# FMC_connector.net
KiCad netlist of a schematic drawn in Altium Designer
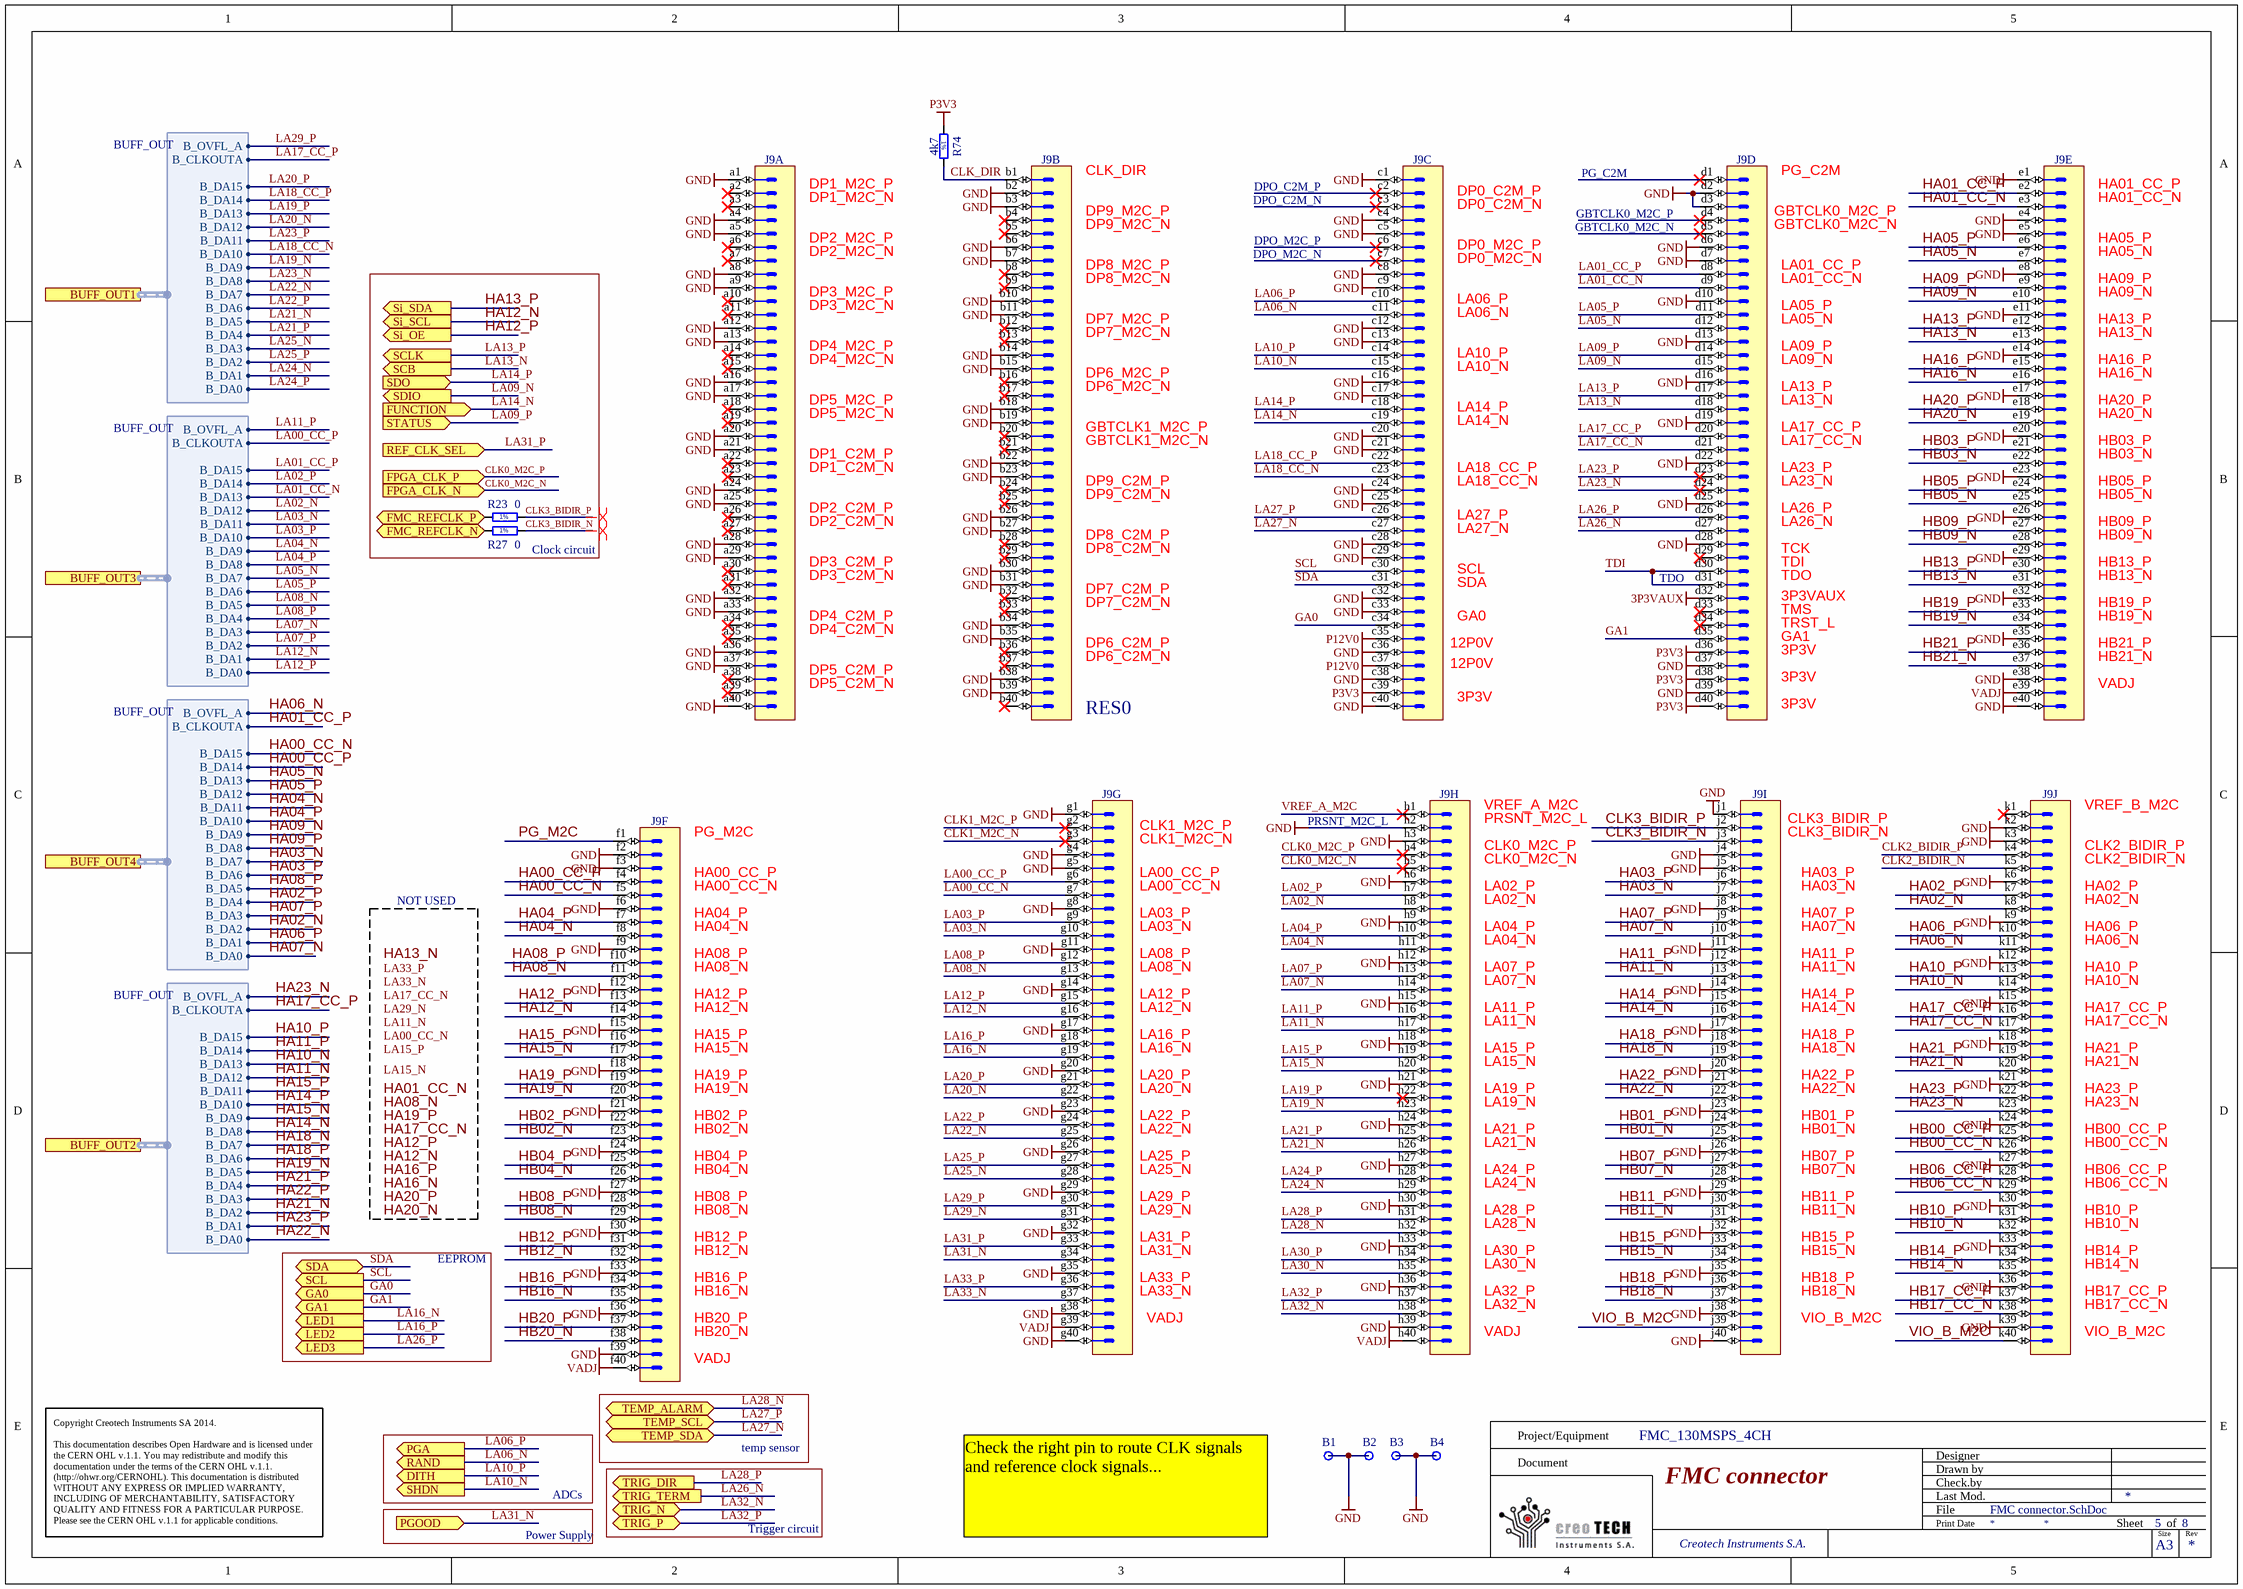
[diagram p0: FMC connector.SchDoc]

(export (version "E")
  (design (tool "Eeschema 10.0.6"))
  (components
    (comp (ref "B1")
      (value "Plated Hole")
      (footprint "MTG300_600")
      (description "Single Terminal Socket")
      (fields (field (name "PART NUMBER") "PLATED_HOLE3.0_PAD6.0") (field (name "AUTHOR") "CERN DEM JLC"))
      (libsource (lib "Eletro-mechanical") (part "Single Terminal Socket"))
    )
    (comp (ref "B2")
      (value "Plated Hole")
      (footprint "MTG300_600")
      (description "Single Terminal Socket")
      (fields (field (name "PART NUMBER") "PLATED_HOLE3.0_PAD6.0") (field (name "AUTHOR") "CERN DEM JLC"))
      (libsource (lib "Eletro-mechanical") (part "Single Terminal Socket"))
    )
    (comp (ref "B3")
      (value "Plated Hole")
      (footprint "MTG300_600")
      (description "Single Terminal Socket")
      (fields (field (name "PART NUMBER") "PLATED_HOLE3.0_PAD6.0") (field (name "AUTHOR") "CERN DEM JLC"))
      (libsource (lib "Eletro-mechanical") (part "Single Terminal Socket"))
    )
    (comp (ref "B4")
      (value "Plated Hole")
      (footprint "MTG300_600")
      (description "Single Terminal Socket")
      (fields (field (name "PART NUMBER") "PLATED_HOLE3.0_PAD6.0") (field (name "AUTHOR") "CERN DEM JLC"))
      (libsource (lib "Eletro-mechanical") (part "Single Terminal Socket"))
    )
    (comp (ref "J9")
      (value "VITA 57")
      (footprint "SAMTEC_ASP-134488-01")
      (description "Connector VITA 57, 400 Male contacts in 10 row abcdefghj")
      (fields
        (field (name "PART NUMBER") "SAMTEC_ASP-134488-01")
        (field (name "MANUFACTURER") "SAMTEC")
        (field (name "AUTHOR") "CERN DEM JLC")
      )
      (libsource (lib "Connectors") (part "Connector VITA 57 400 Male (abcdefghjk)"))
    )
    (comp (ref "R23")
      (value "0")
      (footprint "RESC1005X40N")
      (description "Resistor - 1%")
      (fields
        (field (name "PART NUMBER") "R0402_0R_JUMPER")
        (field (name "MANUFACTURER") "GENERIC")
        (field (name "AUTHOR") "CERN DEM JLC")
      )
      (libsource (lib "Resistors") (part "Resistor - 1%"))
    )
    (comp (ref "R27")
      (value "0")
      (footprint "RESC1005X40N")
      (description "Resistor - 1%")
      (fields
        (field (name "PART NUMBER") "R0402_0R_JUMPER")
        (field (name "MANUFACTURER") "GENERIC")
        (field (name "AUTHOR") "CERN DEM JLC")
      )
      (libsource (lib "Resistors") (part "Resistor - 1%"))
    )
    (comp (ref "R74")
      (value "4k7")
      (footprint "RESC1608X55N")
      (description "Resistor - 1%")
      (fields
        (field (name "PART NUMBER") "R0603_4K7_1%_0.1W_100PPM")
        (field (name "POWER") "0.1W")
        (field (name "AUTHOR") "CERN DEM JLC")
      )
      (libsource (lib "Resistors") (part "Resistor - 1%"))
    )
  )
  (nets
    (net (code "2") (name "/CLK0_M2C_N") (class "Default")
      (node (ref "J9") (pin "h5") (pinfunction "h5_h5") (pintype "bidirectional+no_connect"))
    )
    (net (code "3") (name "/CLK0_M2C_P") (class "Default")
      (node (ref "J9") (pin "h4") (pinfunction "h4_h4") (pintype "bidirectional+no_connect"))
    )
    (net (code "4") (name "/CLK1_M2C_N") (class "Default")
      (node (ref "J9") (pin "g3") (pinfunction "g3_g3") (pintype "bidirectional+no_connect"))
    )
    (net (code "5") (name "/CLK1_M2C_P") (class "Default")
      (node (ref "J9") (pin "g2") (pinfunction "g2_g2") (pintype "bidirectional+no_connect"))
    )
    (net (code "6") (name "/CLK2_BIDIR_N") (class "Default")
      (node (ref "J9") (pin "k5") (pinfunction "k5_k5") (pintype "bidirectional"))
    )
    (net (code "7") (name "/CLK2_BIDIR_P") (class "Default")
      (node (ref "J9") (pin "k4") (pinfunction "k4_k4") (pintype "bidirectional"))
    )
    (net (code "8") (name "/CLK3_BIDIR_N") (class "Default")
      (node (ref "J9") (pin "j3") (pinfunction "j3_j3") (pintype "bidirectional"))
      (node (ref "R27") (pin "2") (pinfunction "2_2") (pintype "passive"))
    )
    (net (code "9") (name "/CLK3_BIDIR_P") (class "Default")
      (node (ref "J9") (pin "j2") (pinfunction "j2_j2") (pintype "bidirectional"))
      (node (ref "R23") (pin "2") (pinfunction "2_2") (pintype "passive"))
    )
    (net (code "10") (name "/CLK_DIR") (class "Default")
      (node (ref "J9") (pin "b1") (pinfunction "b1_b1") (pintype "bidirectional"))
      (node (ref "R74") (pin "2") (pinfunction "2_2") (pintype "passive"))
    )
    (net (code "11") (name "/FMC_REFCLK_N") (class "Default")
      (node (ref "R27") (pin "1") (pinfunction "1_1") (pintype "passive"))
    )
    (net (code "12") (name "/FMC_REFCLK_P") (class "Default")
      (node (ref "R23") (pin "1") (pinfunction "1_1") (pintype "passive"))
    )
    (net (code "13") (name "/GA0") (class "Default")
      (node (ref "J9") (pin "c34") (pinfunction "c34_c34") (pintype "bidirectional"))
    )
    (net (code "14") (name "/GA1") (class "Default")
      (node (ref "J9") (pin "d35") (pinfunction "d35_d35") (pintype "bidirectional"))
    )
    (net (code "15") (name "/HA00_CC_N") (class "Default")
      (node (ref "J9") (pin "f5") (pinfunction "f5_f5") (pintype "bidirectional"))
    )
    (net (code "16") (name "/HA00_CC_P") (class "Default")
      (node (ref "J9") (pin "f4") (pinfunction "f4_f4") (pintype "bidirectional"))
    )
    (net (code "17") (name "/HA01_CC_N") (class "Default")
      (node (ref "J9") (pin "e3") (pinfunction "e3_e3") (pintype "bidirectional"))
    )
    (net (code "18") (name "/HA01_CC_P") (class "Default")
      (node (ref "J9") (pin "e2") (pinfunction "e2_e2") (pintype "bidirectional"))
    )
    (net (code "19") (name "/HA02_N") (class "Default")
      (node (ref "J9") (pin "k8") (pinfunction "k8_k8") (pintype "bidirectional"))
    )
    (net (code "20") (name "/HA02_P") (class "Default")
      (node (ref "J9") (pin "k7") (pinfunction "k7_k7") (pintype "bidirectional"))
    )
    (net (code "21") (name "/HA03_N") (class "Default")
      (node (ref "J9") (pin "j7") (pinfunction "j7_j7") (pintype "bidirectional"))
    )
    (net (code "22") (name "/HA03_P") (class "Default")
      (node (ref "J9") (pin "j6") (pinfunction "j6_j6") (pintype "bidirectional"))
    )
    (net (code "23") (name "/HA04_N") (class "Default")
      (node (ref "J9") (pin "f8") (pinfunction "f8_f8") (pintype "bidirectional"))
    )
    (net (code "24") (name "/HA04_P") (class "Default")
      (node (ref "J9") (pin "f7") (pinfunction "f7_f7") (pintype "bidirectional"))
    )
    (net (code "25") (name "/HA05_N") (class "Default")
      (node (ref "J9") (pin "e7") (pinfunction "e7_e7") (pintype "bidirectional"))
    )
    (net (code "26") (name "/HA05_P") (class "Default")
      (node (ref "J9") (pin "e6") (pinfunction "e6_e6") (pintype "bidirectional"))
    )
    (net (code "27") (name "/HA06_N") (class "Default")
      (node (ref "J9") (pin "k11") (pinfunction "k11_k11") (pintype "bidirectional"))
    )
    (net (code "28") (name "/HA06_P") (class "Default")
      (node (ref "J9") (pin "k10") (pinfunction "k10_k10") (pintype "bidirectional"))
    )
    (net (code "29") (name "/HA07_N") (class "Default")
      (node (ref "J9") (pin "j10") (pinfunction "j10_j10") (pintype "bidirectional"))
    )
    (net (code "30") (name "/HA07_P") (class "Default")
      (node (ref "J9") (pin "j9") (pinfunction "j9_j9") (pintype "bidirectional"))
    )
    (net (code "31") (name "/HA08_N") (class "Default")
      (node (ref "J9") (pin "f11") (pinfunction "f11_f11") (pintype "bidirectional"))
    )
    (net (code "32") (name "/HA08_P") (class "Default")
      (node (ref "J9") (pin "f10") (pinfunction "f10_f10") (pintype "bidirectional"))
    )
    (net (code "33") (name "/HA09_N") (class "Default")
      (node (ref "J9") (pin "e10") (pinfunction "e10_e10") (pintype "bidirectional"))
    )
    (net (code "34") (name "/HA09_P") (class "Default")
      (node (ref "J9") (pin "e9") (pinfunction "e9_e9") (pintype "bidirectional"))
    )
    (net (code "35") (name "/HA10_N") (class "Default")
      (node (ref "J9") (pin "k14") (pinfunction "k14_k14") (pintype "bidirectional"))
    )
    (net (code "36") (name "/HA10_P") (class "Default")
      (node (ref "J9") (pin "k13") (pinfunction "k13_k13") (pintype "bidirectional"))
    )
    (net (code "37") (name "/HA11_N") (class "Default")
      (node (ref "J9") (pin "j13") (pinfunction "j13_j13") (pintype "bidirectional"))
    )
    (net (code "38") (name "/HA11_P") (class "Default")
      (node (ref "J9") (pin "j12") (pinfunction "j12_j12") (pintype "bidirectional"))
    )
    (net (code "39") (name "/HA12_N") (class "Default")
      (node (ref "J9") (pin "f14") (pinfunction "f14_f14") (pintype "bidirectional"))
    )
    (net (code "40") (name "/HA12_P") (class "Default")
      (node (ref "J9") (pin "f13") (pinfunction "f13_f13") (pintype "bidirectional"))
    )
    (net (code "41") (name "/HA13_N") (class "Default")
      (node (ref "J9") (pin "e13") (pinfunction "e13_e13") (pintype "bidirectional"))
    )
    (net (code "42") (name "/HA13_P") (class "Default")
      (node (ref "J9") (pin "e12") (pinfunction "e12_e12") (pintype "bidirectional"))
    )
    (net (code "43") (name "/HA14_N") (class "Default")
      (node (ref "J9") (pin "j16") (pinfunction "j16_j16") (pintype "bidirectional"))
    )
    (net (code "44") (name "/HA14_P") (class "Default")
      (node (ref "J9") (pin "j15") (pinfunction "j15_j15") (pintype "bidirectional"))
    )
    (net (code "45") (name "/HA15_N") (class "Default")
      (node (ref "J9") (pin "f17") (pinfunction "f17_f17") (pintype "bidirectional"))
    )
    (net (code "46") (name "/HA15_P") (class "Default")
      (node (ref "J9") (pin "f16") (pinfunction "f16_f16") (pintype "bidirectional"))
    )
    (net (code "47") (name "/HA16_N") (class "Default")
      (node (ref "J9") (pin "e16") (pinfunction "e16_e16") (pintype "bidirectional"))
    )
    (net (code "48") (name "/HA16_P") (class "Default")
      (node (ref "J9") (pin "e15") (pinfunction "e15_e15") (pintype "bidirectional"))
    )
    (net (code "49") (name "/HA17_CC_N") (class "Default")
      (node (ref "J9") (pin "k17") (pinfunction "k17_k17") (pintype "bidirectional"))
    )
    (net (code "50") (name "/HA17_CC_P") (class "Default")
      (node (ref "J9") (pin "k16") (pinfunction "k16_k16") (pintype "bidirectional"))
    )
    (net (code "51") (name "/HA18_N") (class "Default")
      (node (ref "J9") (pin "j19") (pinfunction "j19_j19") (pintype "bidirectional"))
    )
    (net (code "52") (name "/HA18_P") (class "Default")
      (node (ref "J9") (pin "j18") (pinfunction "j18_j18") (pintype "bidirectional"))
    )
    (net (code "53") (name "/HA19_N") (class "Default")
      (node (ref "J9") (pin "f20") (pinfunction "f20_f20") (pintype "bidirectional"))
    )
    (net (code "54") (name "/HA19_P") (class "Default")
      (node (ref "J9") (pin "f19") (pinfunction "f19_f19") (pintype "bidirectional"))
    )
    (net (code "55") (name "/HA20_N") (class "Default")
      (node (ref "J9") (pin "e19") (pinfunction "e19_e19") (pintype "bidirectional"))
    )
    (net (code "56") (name "/HA20_P") (class "Default")
      (node (ref "J9") (pin "e18") (pinfunction "e18_e18") (pintype "bidirectional"))
    )
    (net (code "57") (name "/HA21_N") (class "Default")
      (node (ref "J9") (pin "k20") (pinfunction "k20_k20") (pintype "bidirectional"))
    )
    (net (code "58") (name "/HA21_P") (class "Default")
      (node (ref "J9") (pin "k19") (pinfunction "k19_k19") (pintype "bidirectional"))
    )
    (net (code "59") (name "/HA22_N") (class "Default")
      (node (ref "J9") (pin "j22") (pinfunction "j22_j22") (pintype "bidirectional"))
    )
    (net (code "60") (name "/HA22_P") (class "Default")
      (node (ref "J9") (pin "j21") (pinfunction "j21_j21") (pintype "bidirectional"))
    )
    (net (code "61") (name "/HA23_N") (class "Default")
      (node (ref "J9") (pin "k23") (pinfunction "k23_k23") (pintype "bidirectional"))
    )
    (net (code "62") (name "/HA23_P") (class "Default")
      (node (ref "J9") (pin "k22") (pinfunction "k22_k22") (pintype "bidirectional"))
    )
    (net (code "63") (name "/HB00_CC_N") (class "Default")
      (node (ref "J9") (pin "k26") (pinfunction "k26_k26") (pintype "bidirectional"))
    )
    (net (code "64") (name "/HB00_CC_P") (class "Default")
      (node (ref "J9") (pin "k25") (pinfunction "k25_k25") (pintype "bidirectional"))
    )
    (net (code "65") (name "/HB01_N") (class "Default")
      (node (ref "J9") (pin "j25") (pinfunction "j25_j25") (pintype "bidirectional"))
    )
    (net (code "66") (name "/HB01_P") (class "Default")
      (node (ref "J9") (pin "j24") (pinfunction "j24_j24") (pintype "bidirectional"))
    )
    (net (code "67") (name "/HB02_N") (class "Default")
      (node (ref "J9") (pin "f23") (pinfunction "f23_f23") (pintype "bidirectional"))
    )
    (net (code "68") (name "/HB02_P") (class "Default")
      (node (ref "J9") (pin "f22") (pinfunction "f22_f22") (pintype "bidirectional"))
    )
    (net (code "69") (name "/HB03_N") (class "Default")
      (node (ref "J9") (pin "e22") (pinfunction "e22_e22") (pintype "bidirectional"))
    )
    (net (code "70") (name "/HB03_P") (class "Default")
      (node (ref "J9") (pin "e21") (pinfunction "e21_e21") (pintype "bidirectional"))
    )
    (net (code "71") (name "/HB04_N") (class "Default")
      (node (ref "J9") (pin "f26") (pinfunction "f26_f26") (pintype "bidirectional"))
    )
    (net (code "72") (name "/HB04_P") (class "Default")
      (node (ref "J9") (pin "f25") (pinfunction "f25_f25") (pintype "bidirectional"))
    )
    (net (code "73") (name "/HB05_N") (class "Default")
      (node (ref "J9") (pin "e25") (pinfunction "e25_e25") (pintype "bidirectional"))
    )
    (net (code "74") (name "/HB05_P") (class "Default")
      (node (ref "J9") (pin "e24") (pinfunction "e24_e24") (pintype "bidirectional"))
    )
    (net (code "75") (name "/HB06_CC_N") (class "Default")
      (node (ref "J9") (pin "k29") (pinfunction "k29_k29") (pintype "bidirectional"))
    )
    (net (code "76") (name "/HB06_CC_P") (class "Default")
      (node (ref "J9") (pin "k28") (pinfunction "k28_k28") (pintype "bidirectional"))
    )
    (net (code "77") (name "/HB07_N") (class "Default")
      (node (ref "J9") (pin "j28") (pinfunction "j28_j28") (pintype "bidirectional"))
    )
    (net (code "78") (name "/HB07_P") (class "Default")
      (node (ref "J9") (pin "j27") (pinfunction "j27_j27") (pintype "bidirectional"))
    )
    (net (code "79") (name "/HB08_N") (class "Default")
      (node (ref "J9") (pin "f29") (pinfunction "f29_f29") (pintype "bidirectional"))
    )
    (net (code "80") (name "/HB08_P") (class "Default")
      (node (ref "J9") (pin "f28") (pinfunction "f28_f28") (pintype "bidirectional"))
    )
    (net (code "81") (name "/HB09_N") (class "Default")
      (node (ref "J9") (pin "e28") (pinfunction "e28_e28") (pintype "bidirectional"))
    )
    (net (code "82") (name "/HB09_P") (class "Default")
      (node (ref "J9") (pin "e27") (pinfunction "e27_e27") (pintype "bidirectional"))
    )
    (net (code "83") (name "/HB10_N") (class "Default")
      (node (ref "J9") (pin "k32") (pinfunction "k32_k32") (pintype "bidirectional"))
    )
    (net (code "84") (name "/HB10_P") (class "Default")
      (node (ref "J9") (pin "k31") (pinfunction "k31_k31") (pintype "bidirectional"))
    )
    (net (code "85") (name "/HB11_N") (class "Default")
      (node (ref "J9") (pin "j31") (pinfunction "j31_j31") (pintype "bidirectional"))
    )
    (net (code "86") (name "/HB11_P") (class "Default")
      (node (ref "J9") (pin "j30") (pinfunction "j30_j30") (pintype "bidirectional"))
    )
    (net (code "87") (name "/HB12_N") (class "Default")
      (node (ref "J9") (pin "f32") (pinfunction "f32_f32") (pintype "bidirectional"))
    )
    (net (code "88") (name "/HB12_P") (class "Default")
      (node (ref "J9") (pin "f31") (pinfunction "f31_f31") (pintype "bidirectional"))
    )
    (net (code "89") (name "/HB13_N") (class "Default")
      (node (ref "J9") (pin "e31") (pinfunction "e31_e31") (pintype "bidirectional"))
    )
    (net (code "90") (name "/HB13_P") (class "Default")
      (node (ref "J9") (pin "e30") (pinfunction "e30_e30") (pintype "bidirectional"))
    )
    (net (code "91") (name "/HB14_N") (class "Default")
      (node (ref "J9") (pin "k35") (pinfunction "k35_k35") (pintype "bidirectional"))
    )
    (net (code "92") (name "/HB14_P") (class "Default")
      (node (ref "J9") (pin "k34") (pinfunction "k34_k34") (pintype "bidirectional"))
    )
    (net (code "93") (name "/HB15_N") (class "Default")
      (node (ref "J9") (pin "j34") (pinfunction "j34_j34") (pintype "bidirectional"))
    )
    (net (code "94") (name "/HB15_P") (class "Default")
      (node (ref "J9") (pin "j33") (pinfunction "j33_j33") (pintype "bidirectional"))
    )
    (net (code "95") (name "/HB16_N") (class "Default")
      (node (ref "J9") (pin "f35") (pinfunction "f35_f35") (pintype "bidirectional"))
    )
    (net (code "96") (name "/HB16_P") (class "Default")
      (node (ref "J9") (pin "f34") (pinfunction "f34_f34") (pintype "bidirectional"))
    )
    (net (code "97") (name "/HB17_CC_N") (class "Default")
      (node (ref "J9") (pin "k38") (pinfunction "k38_k38") (pintype "bidirectional"))
    )
    (net (code "98") (name "/HB17_CC_P") (class "Default")
      (node (ref "J9") (pin "k37") (pinfunction "k37_k37") (pintype "bidirectional"))
    )
    (net (code "99") (name "/HB18_N") (class "Default")
      (node (ref "J9") (pin "j37") (pinfunction "j37_j37") (pintype "bidirectional"))
    )
    (net (code "100") (name "/HB18_P") (class "Default")
      (node (ref "J9") (pin "j36") (pinfunction "j36_j36") (pintype "bidirectional"))
    )
    (net (code "101") (name "/HB19_N") (class "Default")
      (node (ref "J9") (pin "e34") (pinfunction "e34_e34") (pintype "bidirectional"))
    )
    (net (code "102") (name "/HB19_P") (class "Default")
      (node (ref "J9") (pin "e33") (pinfunction "e33_e33") (pintype "bidirectional"))
    )
    (net (code "103") (name "/HB20_N") (class "Default")
      (node (ref "J9") (pin "f38") (pinfunction "f38_f38") (pintype "bidirectional"))
    )
    (net (code "104") (name "/HB20_P") (class "Default")
      (node (ref "J9") (pin "f37") (pinfunction "f37_f37") (pintype "bidirectional"))
    )
    (net (code "105") (name "/HB21_N") (class "Default")
      (node (ref "J9") (pin "e37") (pinfunction "e37_e37") (pintype "bidirectional"))
    )
    (net (code "106") (name "/HB21_P") (class "Default")
      (node (ref "J9") (pin "e36") (pinfunction "e36_e36") (pintype "bidirectional"))
    )
    (net (code "107") (name "/LA00_CC_N") (class "Default")
      (node (ref "J9") (pin "g7") (pinfunction "g7_g7") (pintype "bidirectional"))
    )
    (net (code "108") (name "/LA00_CC_P") (class "Default")
      (node (ref "J9") (pin "g6") (pinfunction "g6_g6") (pintype "bidirectional"))
    )
    (net (code "109") (name "/LA01_CC_N") (class "Default")
      (node (ref "J9") (pin "d9") (pinfunction "d9_d9") (pintype "bidirectional"))
    )
    (net (code "110") (name "/LA01_CC_P") (class "Default")
      (node (ref "J9") (pin "d8") (pinfunction "d8_d8") (pintype "bidirectional"))
    )
    (net (code "111") (name "/LA02_N") (class "Default")
      (node (ref "J9") (pin "h8") (pinfunction "h8_h8") (pintype "bidirectional"))
    )
    (net (code "112") (name "/LA02_P") (class "Default")
      (node (ref "J9") (pin "h7") (pinfunction "h7_h7") (pintype "bidirectional"))
    )
    (net (code "113") (name "/LA03_N") (class "Default")
      (node (ref "J9") (pin "g10") (pinfunction "g10_g10") (pintype "bidirectional"))
    )
    (net (code "114") (name "/LA03_P") (class "Default")
      (node (ref "J9") (pin "g9") (pinfunction "g9_g9") (pintype "bidirectional"))
    )
    (net (code "115") (name "/LA04_N") (class "Default")
      (node (ref "J9") (pin "h11") (pinfunction "h11_h11") (pintype "bidirectional"))
    )
    (net (code "116") (name "/LA04_P") (class "Default")
      (node (ref "J9") (pin "h10") (pinfunction "h10_h10") (pintype "bidirectional"))
    )
    (net (code "117") (name "/LA05_N") (class "Default")
      (node (ref "J9") (pin "d12") (pinfunction "d12_d12") (pintype "bidirectional"))
    )
    (net (code "118") (name "/LA05_P") (class "Default")
      (node (ref "J9") (pin "d11") (pinfunction "d11_d11") (pintype "bidirectional"))
    )
    (net (code "119") (name "/LA06_N") (class "Default")
      (node (ref "J9") (pin "c11") (pinfunction "c11_c11") (pintype "bidirectional"))
    )
    (net (code "120") (name "/LA06_P") (class "Default")
      (node (ref "J9") (pin "c10") (pinfunction "c10_c10") (pintype "bidirectional"))
    )
    (net (code "121") (name "/LA07_N") (class "Default")
      (node (ref "J9") (pin "h14") (pinfunction "h14_h14") (pintype "bidirectional"))
    )
    (net (code "122") (name "/LA07_P") (class "Default")
      (node (ref "J9") (pin "h13") (pinfunction "h13_h13") (pintype "bidirectional"))
    )
    (net (code "123") (name "/LA08_N") (class "Default")
      (node (ref "J9") (pin "g13") (pinfunction "g13_g13") (pintype "bidirectional"))
    )
    (net (code "124") (name "/LA08_P") (class "Default")
      (node (ref "J9") (pin "g12") (pinfunction "g12_g12") (pintype "bidirectional"))
    )
    (net (code "125") (name "/LA09_N") (class "Default")
      (node (ref "J9") (pin "d15") (pinfunction "d15_d15") (pintype "bidirectional"))
    )
    (net (code "126") (name "/LA09_P") (class "Default")
      (node (ref "J9") (pin "d14") (pinfunction "d14_d14") (pintype "bidirectional"))
    )
    (net (code "127") (name "/LA10_N") (class "Default")
      (node (ref "J9") (pin "c15") (pinfunction "c15_c15") (pintype "bidirectional"))
    )
    (net (code "128") (name "/LA10_P") (class "Default")
      (node (ref "J9") (pin "c14") (pinfunction "c14_c14") (pintype "bidirectional"))
    )
    (net (code "129") (name "/LA11_N") (class "Default")
      (node (ref "J9") (pin "h17") (pinfunction "h17_h17") (pintype "bidirectional"))
    )
    (net (code "130") (name "/LA11_P") (class "Default")
      (node (ref "J9") (pin "h16") (pinfunction "h16_h16") (pintype "bidirectional"))
    )
    (net (code "131") (name "/LA12_N") (class "Default")
      (node (ref "J9") (pin "g16") (pinfunction "g16_g16") (pintype "bidirectional"))
    )
    (net (code "132") (name "/LA12_P") (class "Default")
      (node (ref "J9") (pin "g15") (pinfunction "g15_g15") (pintype "bidirectional"))
    )
    (net (code "133") (name "/LA13_N") (class "Default")
      (node (ref "J9") (pin "d18") (pinfunction "d18_d18") (pintype "bidirectional"))
    )
    (net (code "134") (name "/LA13_P") (class "Default")
      (node (ref "J9") (pin "d17") (pinfunction "d17_d17") (pintype "bidirectional"))
    )
    (net (code "135") (name "/LA14_N") (class "Default")
      (node (ref "J9") (pin "c19") (pinfunction "c19_c19") (pintype "bidirectional"))
    )
    (net (code "136") (name "/LA14_P") (class "Default")
      (node (ref "J9") (pin "c18") (pinfunction "c18_c18") (pintype "bidirectional"))
    )
    (net (code "137") (name "/LA15_N") (class "Default")
      (node (ref "J9") (pin "h20") (pinfunction "h20_h20") (pintype "bidirectional"))
    )
    (net (code "138") (name "/LA15_P") (class "Default")
      (node (ref "J9") (pin "h19") (pinfunction "h19_h19") (pintype "bidirectional"))
    )
    (net (code "139") (name "/LA16_N") (class "Default")
      (node (ref "J9") (pin "g19") (pinfunction "g19_g19") (pintype "bidirectional"))
    )
    (net (code "140") (name "/LA16_P") (class "Default")
      (node (ref "J9") (pin "g18") (pinfunction "g18_g18") (pintype "bidirectional"))
    )
    (net (code "141") (name "/LA17_CC_N") (class "Default")
      (node (ref "J9") (pin "d21") (pinfunction "d21_d21") (pintype "bidirectional"))
    )
    (net (code "142") (name "/LA17_CC_P") (class "Default")
      (node (ref "J9") (pin "d20") (pinfunction "d20_d20") (pintype "bidirectional"))
    )
    (net (code "143") (name "/LA18_CC_N") (class "Default")
      (node (ref "J9") (pin "c23") (pinfunction "c23_c23") (pintype "bidirectional"))
    )
    (net (code "144") (name "/LA18_CC_P") (class "Default")
      (node (ref "J9") (pin "c22") (pinfunction "c22_c22") (pintype "bidirectional"))
    )
    (net (code "145") (name "/LA19_N") (class "Default")
      (node (ref "J9") (pin "h23") (pinfunction "h23_h23") (pintype "bidirectional"))
    )
    (net (code "146") (name "/LA19_P") (class "Default")
      (node (ref "J9") (pin "h22") (pinfunction "h22_h22") (pintype "bidirectional+no_connect"))
    )
    (net (code "147") (name "/LA20_N") (class "Default")
      (node (ref "J9") (pin "g22") (pinfunction "g22_g22") (pintype "bidirectional"))
    )
    (net (code "148") (name "/LA20_P") (class "Default")
      (node (ref "J9") (pin "g21") (pinfunction "g21_g21") (pintype "bidirectional"))
    )
    (net (code "149") (name "/LA21_N") (class "Default")
      (node (ref "J9") (pin "h26") (pinfunction "h26_h26") (pintype "bidirectional"))
    )
    (net (code "150") (name "/LA21_P") (class "Default")
      (node (ref "J9") (pin "h25") (pinfunction "h25_h25") (pintype "bidirectional"))
    )
    (net (code "151") (name "/LA22_N") (class "Default")
      (node (ref "J9") (pin "g25") (pinfunction "g25_g25") (pintype "bidirectional"))
    )
    (net (code "152") (name "/LA22_P") (class "Default")
      (node (ref "J9") (pin "g24") (pinfunction "g24_g24") (pintype "bidirectional"))
    )
    (net (code "153") (name "/LA23_N") (class "Default")
      (node (ref "J9") (pin "d24") (pinfunction "d24_d24") (pintype "bidirectional+no_connect"))
    )
    (net (code "154") (name "/LA23_P") (class "Default")
      (node (ref "J9") (pin "d23") (pinfunction "d23_d23") (pintype "bidirectional+no_connect"))
    )
    (net (code "155") (name "/LA24_N") (class "Default")
      (node (ref "J9") (pin "h29") (pinfunction "h29_h29") (pintype "bidirectional"))
    )
    (net (code "156") (name "/LA24_P") (class "Default")
      (node (ref "J9") (pin "h28") (pinfunction "h28_h28") (pintype "bidirectional"))
    )
    (net (code "157") (name "/LA25_N") (class "Default")
      (node (ref "J9") (pin "g28") (pinfunction "g28_g28") (pintype "bidirectional"))
    )
    (net (code "158") (name "/LA25_P") (class "Default")
      (node (ref "J9") (pin "g27") (pinfunction "g27_g27") (pintype "bidirectional"))
    )
    (net (code "159") (name "/LA26_N") (class "Default")
      (node (ref "J9") (pin "d27") (pinfunction "d27_d27") (pintype "bidirectional"))
    )
    (net (code "160") (name "/LA26_P") (class "Default")
      (node (ref "J9") (pin "d26") (pinfunction "d26_d26") (pintype "bidirectional"))
    )
    (net (code "161") (name "/LA27_N") (class "Default")
      (node (ref "J9") (pin "c27") (pinfunction "c27_c27") (pintype "bidirectional"))
    )
    (net (code "162") (name "/LA27_P") (class "Default")
      (node (ref "J9") (pin "c26") (pinfunction "c26_c26") (pintype "bidirectional"))
    )
    (net (code "163") (name "/LA28_N") (class "Default")
      (node (ref "J9") (pin "h32") (pinfunction "h32_h32") (pintype "bidirectional"))
    )
    (net (code "164") (name "/LA28_P") (class "Default")
      (node (ref "J9") (pin "h31") (pinfunction "h31_h31") (pintype "bidirectional"))
    )
    (net (code "165") (name "/LA29_N") (class "Default")
      (node (ref "J9") (pin "g31") (pinfunction "g31_g31") (pintype "bidirectional"))
    )
    (net (code "166") (name "/LA29_P") (class "Default")
      (node (ref "J9") (pin "g30") (pinfunction "g30_g30") (pintype "bidirectional"))
    )
    (net (code "167") (name "/LA30_N") (class "Default")
      (node (ref "J9") (pin "h35") (pinfunction "h35_h35") (pintype "bidirectional"))
    )
    (net (code "168") (name "/LA30_P") (class "Default")
      (node (ref "J9") (pin "h34") (pinfunction "h34_h34") (pintype "bidirectional"))
    )
    (net (code "169") (name "/LA31_N") (class "Default")
      (node (ref "J9") (pin "g34") (pinfunction "g34_g34") (pintype "bidirectional"))
    )
    (net (code "170") (name "/LA31_P") (class "Default")
      (node (ref "J9") (pin "g33") (pinfunction "g33_g33") (pintype "bidirectional"))
    )
    (net (code "171") (name "/LA32_N") (class "Default")
      (node (ref "J9") (pin "h38") (pinfunction "h38_h38") (pintype "bidirectional"))
    )
    (net (code "172") (name "/LA32_P") (class "Default")
      (node (ref "J9") (pin "h37") (pinfunction "h37_h37") (pintype "bidirectional"))
    )
    (net (code "173") (name "/LA33_N") (class "Default")
      (node (ref "J9") (pin "g37") (pinfunction "g37_g37") (pintype "bidirectional"))
    )
    (net (code "174") (name "/LA33_P") (class "Default")
      (node (ref "J9") (pin "g36") (pinfunction "g36_g36") (pintype "bidirectional"))
    )
    (net (code "175") (name "/PG_M2C") (class "Default")
      (node (ref "J9") (pin "f1") (pinfunction "f1_f1") (pintype "bidirectional"))
    )
    (net (code "176") (name "/SCL") (class "Default")
      (node (ref "J9") (pin "c30") (pinfunction "c30_c30") (pintype "bidirectional"))
    )
    (net (code "177") (name "/SDA") (class "Default")
      (node (ref "J9") (pin "c31") (pinfunction "c31_c31") (pintype "bidirectional"))
    )
    (net (code "178") (name "/TDI") (class "Default")
      (node (ref "J9") (pin "d30") (pinfunction "d30_d30") (pintype "bidirectional"))
      (node (ref "J9") (pin "d31") (pinfunction "d31_d31") (pintype "bidirectional"))
    )
    (net (code "179") (name "/VIO_B_M2C") (class "Default")
      (node (ref "J9") (pin "j39") (pinfunction "j39_j39") (pintype "bidirectional"))
      (node (ref "J9") (pin "k40") (pinfunction "k40_k40") (pintype "bidirectional"))
    )
    (net (code "180") (name "/VREF_A_M2C") (class "Default")
      (node (ref "J9") (pin "h1") (pinfunction "h1_h1") (pintype "bidirectional+no_connect"))
    )
    (net (code "182") (name "3P3VAUX") (class "Default")
      (node (ref "J9") (pin "d32") (pinfunction "d32_d32") (pintype "bidirectional"))
    )
    (net (code "183") (name "GND") (class "Default")
      (node (ref "B1") (pin "1") (pinfunction "1_1") (pintype "bidirectional"))
      (node (ref "B2") (pin "1") (pinfunction "1_1") (pintype "bidirectional"))
      (node (ref "B3") (pin "1") (pinfunction "1_1") (pintype "bidirectional"))
      (node (ref "B4") (pin "1") (pinfunction "1_1") (pintype "bidirectional"))
      (node (ref "J9") (pin "a1") (pinfunction "a1_a1") (pintype "bidirectional"))
      (node (ref "J9") (pin "a12") (pinfunction "a12_a12") (pintype "bidirectional"))
      (node (ref "J9") (pin "a13") (pinfunction "a13_a13") (pintype "bidirectional"))
      (node (ref "J9") (pin "a16") (pinfunction "a16_a16") (pintype "bidirectional"))
      (node (ref "J9") (pin "a17") (pinfunction "a17_a17") (pintype "bidirectional"))
      (node (ref "J9") (pin "a20") (pinfunction "a20_a20") (pintype "bidirectional"))
      (node (ref "J9") (pin "a21") (pinfunction "a21_a21") (pintype "bidirectional"))
      (node (ref "J9") (pin "a24") (pinfunction "a24_a24") (pintype "bidirectional"))
      (node (ref "J9") (pin "a25") (pinfunction "a25_a25") (pintype "bidirectional"))
      (node (ref "J9") (pin "a28") (pinfunction "a28_a28") (pintype "bidirectional"))
      (node (ref "J9") (pin "a29") (pinfunction "a29_a29") (pintype "bidirectional"))
      (node (ref "J9") (pin "a32") (pinfunction "a32_a32") (pintype "bidirectional"))
      (node (ref "J9") (pin "a33") (pinfunction "a33_a33") (pintype "bidirectional"))
      (node (ref "J9") (pin "a36") (pinfunction "a36_a36") (pintype "bidirectional"))
      (node (ref "J9") (pin "a37") (pinfunction "a37_a37") (pintype "bidirectional"))
      (node (ref "J9") (pin "a4") (pinfunction "a4_a4") (pintype "bidirectional"))
      (node (ref "J9") (pin "a40") (pinfunction "a40_a40") (pintype "bidirectional"))
      (node (ref "J9") (pin "a5") (pinfunction "a5_a5") (pintype "bidirectional"))
      (node (ref "J9") (pin "a8") (pinfunction "a8_a8") (pintype "bidirectional"))
      (node (ref "J9") (pin "a9") (pinfunction "a9_a9") (pintype "bidirectional"))
      (node (ref "J9") (pin "b10") (pinfunction "b10_b10") (pintype "bidirectional"))
      (node (ref "J9") (pin "b11") (pinfunction "b11_b11") (pintype "bidirectional"))
      (node (ref "J9") (pin "b14") (pinfunction "b14_b14") (pintype "bidirectional"))
      (node (ref "J9") (pin "b15") (pinfunction "b15_b15") (pintype "bidirectional"))
      (node (ref "J9") (pin "b18") (pinfunction "b18_b18") (pintype "bidirectional"))
      (node (ref "J9") (pin "b19") (pinfunction "b19_b19") (pintype "bidirectional"))
      (node (ref "J9") (pin "b2") (pinfunction "b2_b2") (pintype "bidirectional"))
      (node (ref "J9") (pin "b22") (pinfunction "b22_b22") (pintype "bidirectional"))
      (node (ref "J9") (pin "b23") (pinfunction "b23_b23") (pintype "bidirectional"))
      (node (ref "J9") (pin "b26") (pinfunction "b26_b26") (pintype "bidirectional"))
      (node (ref "J9") (pin "b27") (pinfunction "b27_b27") (pintype "bidirectional"))
      (node (ref "J9") (pin "b3") (pinfunction "b3_b3") (pintype "bidirectional"))
      (node (ref "J9") (pin "b30") (pinfunction "b30_b30") (pintype "bidirectional"))
      (node (ref "J9") (pin "b31") (pinfunction "b31_b31") (pintype "bidirectional"))
      (node (ref "J9") (pin "b34") (pinfunction "b34_b34") (pintype "bidirectional"))
      (node (ref "J9") (pin "b35") (pinfunction "b35_b35") (pintype "bidirectional"))
      (node (ref "J9") (pin "b38") (pinfunction "b38_b38") (pintype "bidirectional"))
      (node (ref "J9") (pin "b39") (pinfunction "b39_b39") (pintype "bidirectional"))
      (node (ref "J9") (pin "b6") (pinfunction "b6_b6") (pintype "bidirectional"))
      (node (ref "J9") (pin "b7") (pinfunction "b7_b7") (pintype "bidirectional"))
      (node (ref "J9") (pin "c1") (pinfunction "c1_c1") (pintype "bidirectional"))
      (node (ref "J9") (pin "c12") (pinfunction "c12_c12") (pintype "bidirectional"))
      (node (ref "J9") (pin "c13") (pinfunction "c13_c13") (pintype "bidirectional"))
      (node (ref "J9") (pin "c16") (pinfunction "c16_c16") (pintype "bidirectional"))
      (node (ref "J9") (pin "c17") (pinfunction "c17_c17") (pintype "bidirectional"))
      (node (ref "J9") (pin "c20") (pinfunction "c20_c20") (pintype "bidirectional"))
      (node (ref "J9") (pin "c21") (pinfunction "c21_c21") (pintype "bidirectional"))
      (node (ref "J9") (pin "c24") (pinfunction "c24_c24") (pintype "bidirectional"))
      (node (ref "J9") (pin "c25") (pinfunction "c25_c25") (pintype "bidirectional"))
      (node (ref "J9") (pin "c28") (pinfunction "c28_c28") (pintype "bidirectional"))
      (node (ref "J9") (pin "c29") (pinfunction "c29_c29") (pintype "bidirectional"))
      (node (ref "J9") (pin "c32") (pinfunction "c32_c32") (pintype "bidirectional"))
      (node (ref "J9") (pin "c33") (pinfunction "c33_c33") (pintype "bidirectional"))
      (node (ref "J9") (pin "c36") (pinfunction "c36_c36") (pintype "bidirectional"))
      (node (ref "J9") (pin "c38") (pinfunction "c38_c38") (pintype "bidirectional"))
      (node (ref "J9") (pin "c4") (pinfunction "c4_c4") (pintype "bidirectional"))
      (node (ref "J9") (pin "c40") (pinfunction "c40_c40") (pintype "bidirectional"))
      (node (ref "J9") (pin "c5") (pinfunction "c5_c5") (pintype "bidirectional"))
      (node (ref "J9") (pin "c8") (pinfunction "c8_c8") (pintype "bidirectional"))
      (node (ref "J9") (pin "c9") (pinfunction "c9_c9") (pintype "bidirectional"))
      (node (ref "J9") (pin "d10") (pinfunction "d10_d10") (pintype "bidirectional"))
      (node (ref "J9") (pin "d13") (pinfunction "d13_d13") (pintype "bidirectional"))
      (node (ref "J9") (pin "d16") (pinfunction "d16_d16") (pintype "bidirectional"))
      (node (ref "J9") (pin "d19") (pinfunction "d19_d19") (pintype "bidirectional"))
      (node (ref "J9") (pin "d2") (pinfunction "d2_d2") (pintype "bidirectional"))
      (node (ref "J9") (pin "d22") (pinfunction "d22_d22") (pintype "bidirectional"))
      (node (ref "J9") (pin "d25") (pinfunction "d25_d25") (pintype "bidirectional"))
      (node (ref "J9") (pin "d28") (pinfunction "d28_d28") (pintype "bidirectional"))
      (node (ref "J9") (pin "d3") (pinfunction "d3_d3") (pintype "bidirectional"))
      (node (ref "J9") (pin "d37") (pinfunction "d37_d37") (pintype "bidirectional"))
      (node (ref "J9") (pin "d39") (pinfunction "d39_d39") (pintype "bidirectional"))
      (node (ref "J9") (pin "d6") (pinfunction "d6_d6") (pintype "bidirectional"))
      (node (ref "J9") (pin "d7") (pinfunction "d7_d7") (pintype "bidirectional"))
      (node (ref "J9") (pin "e1") (pinfunction "e1_e1") (pintype "bidirectional"))
      (node (ref "J9") (pin "e11") (pinfunction "e11_e11") (pintype "bidirectional"))
      (node (ref "J9") (pin "e14") (pinfunction "e14_e14") (pintype "bidirectional"))
      (node (ref "J9") (pin "e17") (pinfunction "e17_e17") (pintype "bidirectional"))
      (node (ref "J9") (pin "e20") (pinfunction "e20_e20") (pintype "bidirectional"))
      (node (ref "J9") (pin "e23") (pinfunction "e23_e23") (pintype "bidirectional"))
      (node (ref "J9") (pin "e26") (pinfunction "e26_e26") (pintype "bidirectional"))
      (node (ref "J9") (pin "e29") (pinfunction "e29_e29") (pintype "bidirectional"))
      (node (ref "J9") (pin "e32") (pinfunction "e32_e32") (pintype "bidirectional"))
      (node (ref "J9") (pin "e35") (pinfunction "e35_e35") (pintype "bidirectional"))
      (node (ref "J9") (pin "e38") (pinfunction "e38_e38") (pintype "bidirectional"))
      (node (ref "J9") (pin "e4") (pinfunction "e4_e4") (pintype "bidirectional"))
      (node (ref "J9") (pin "e40") (pinfunction "e40_e40") (pintype "bidirectional"))
      (node (ref "J9") (pin "e5") (pinfunction "e5_e5") (pintype "bidirectional"))
      (node (ref "J9") (pin "e8") (pinfunction "e8_e8") (pintype "bidirectional"))
      (node (ref "J9") (pin "f12") (pinfunction "f12_f12") (pintype "bidirectional"))
      (node (ref "J9") (pin "f15") (pinfunction "f15_f15") (pintype "bidirectional"))
      (node (ref "J9") (pin "f18") (pinfunction "f18_f18") (pintype "bidirectional"))
      (node (ref "J9") (pin "f2") (pinfunction "f2_f2") (pintype "bidirectional"))
      (node (ref "J9") (pin "f21") (pinfunction "f21_f21") (pintype "bidirectional"))
      (node (ref "J9") (pin "f24") (pinfunction "f24_f24") (pintype "bidirectional"))
      (node (ref "J9") (pin "f27") (pinfunction "f27_f27") (pintype "bidirectional"))
      (node (ref "J9") (pin "f3") (pinfunction "f3_f3") (pintype "bidirectional"))
      (node (ref "J9") (pin "f30") (pinfunction "f30_f30") (pintype "bidirectional"))
      (node (ref "J9") (pin "f33") (pinfunction "f33_f33") (pintype "bidirectional"))
      (node (ref "J9") (pin "f36") (pinfunction "f36_f36") (pintype "bidirectional"))
      (node (ref "J9") (pin "f39") (pinfunction "f39_f39") (pintype "bidirectional"))
      (node (ref "J9") (pin "f6") (pinfunction "f6_f6") (pintype "bidirectional"))
      (node (ref "J9") (pin "f9") (pinfunction "f9_f9") (pintype "bidirectional"))
      (node (ref "J9") (pin "g1") (pinfunction "g1_g1") (pintype "bidirectional"))
      (node (ref "J9") (pin "g11") (pinfunction "g11_g11") (pintype "bidirectional"))
      (node (ref "J9") (pin "g14") (pinfunction "g14_g14") (pintype "bidirectional"))
      (node (ref "J9") (pin "g17") (pinfunction "g17_g17") (pintype "bidirectional"))
      (node (ref "J9") (pin "g20") (pinfunction "g20_g20") (pintype "bidirectional"))
      (node (ref "J9") (pin "g23") (pinfunction "g23_g23") (pintype "bidirectional"))
      (node (ref "J9") (pin "g26") (pinfunction "g26_g26") (pintype "bidirectional"))
      (node (ref "J9") (pin "g29") (pinfunction "g29_g29") (pintype "bidirectional"))
      (node (ref "J9") (pin "g32") (pinfunction "g32_g32") (pintype "bidirectional"))
      (node (ref "J9") (pin "g35") (pinfunction "g35_g35") (pintype "bidirectional"))
      (node (ref "J9") (pin "g38") (pinfunction "g38_g38") (pintype "bidirectional"))
      (node (ref "J9") (pin "g4") (pinfunction "g4_g4") (pintype "bidirectional"))
      (node (ref "J9") (pin "g40") (pinfunction "g40_g40") (pintype "bidirectional"))
      (node (ref "J9") (pin "g5") (pinfunction "g5_g5") (pintype "bidirectional"))
      (node (ref "J9") (pin "g8") (pinfunction "g8_g8") (pintype "bidirectional"))
      (node (ref "J9") (pin "h12") (pinfunction "h12_h12") (pintype "bidirectional"))
      (node (ref "J9") (pin "h15") (pinfunction "h15_h15") (pintype "bidirectional"))
      (node (ref "J9") (pin "h18") (pinfunction "h18_h18") (pintype "bidirectional"))
      (node (ref "J9") (pin "h2") (pinfunction "h2_h2") (pintype "bidirectional"))
      (node (ref "J9") (pin "h21") (pinfunction "h21_h21") (pintype "bidirectional"))
      (node (ref "J9") (pin "h24") (pinfunction "h24_h24") (pintype "bidirectional"))
      (node (ref "J9") (pin "h27") (pinfunction "h27_h27") (pintype "bidirectional"))
      (node (ref "J9") (pin "h3") (pinfunction "h3_h3") (pintype "bidirectional"))
      (node (ref "J9") (pin "h30") (pinfunction "h30_h30") (pintype "bidirectional"))
      (node (ref "J9") (pin "h33") (pinfunction "h33_h33") (pintype "bidirectional"))
      (node (ref "J9") (pin "h36") (pinfunction "h36_h36") (pintype "bidirectional"))
      (node (ref "J9") (pin "h39") (pinfunction "h39_h39") (pintype "bidirectional"))
      (node (ref "J9") (pin "h6") (pinfunction "h6_h6") (pintype "bidirectional"))
      (node (ref "J9") (pin "h9") (pinfunction "h9_h9") (pintype "bidirectional"))
      (node (ref "J9") (pin "j1") (pinfunction "j1_j1") (pintype "bidirectional"))
      (node (ref "J9") (pin "j11") (pinfunction "j11_j11") (pintype "bidirectional"))
      (node (ref "J9") (pin "j14") (pinfunction "j14_j14") (pintype "bidirectional"))
      (node (ref "J9") (pin "j17") (pinfunction "j17_j17") (pintype "bidirectional"))
      (node (ref "J9") (pin "j20") (pinfunction "j20_j20") (pintype "bidirectional"))
      (node (ref "J9") (pin "j23") (pinfunction "j23_j23") (pintype "bidirectional"))
      (node (ref "J9") (pin "j26") (pinfunction "j26_j26") (pintype "bidirectional"))
      (node (ref "J9") (pin "j29") (pinfunction "j29_j29") (pintype "bidirectional"))
      (node (ref "J9") (pin "j32") (pinfunction "j32_j32") (pintype "bidirectional"))
      (node (ref "J9") (pin "j35") (pinfunction "j35_j35") (pintype "bidirectional"))
      (node (ref "J9") (pin "j38") (pinfunction "j38_j38") (pintype "bidirectional"))
      (node (ref "J9") (pin "j4") (pinfunction "j4_j4") (pintype "bidirectional"))
      (node (ref "J9") (pin "j40") (pinfunction "j40_j40") (pintype "bidirectional"))
      (node (ref "J9") (pin "j5") (pinfunction "j5_j5") (pintype "bidirectional"))
      (node (ref "J9") (pin "j8") (pinfunction "j8_j8") (pintype "bidirectional"))
      (node (ref "J9") (pin "k12") (pinfunction "k12_k12") (pintype "bidirectional"))
      (node (ref "J9") (pin "k15") (pinfunction "k15_k15") (pintype "bidirectional"))
      (node (ref "J9") (pin "k18") (pinfunction "k18_k18") (pintype "bidirectional"))
      (node (ref "J9") (pin "k2") (pinfunction "k2_k2") (pintype "bidirectional"))
      (node (ref "J9") (pin "k21") (pinfunction "k21_k21") (pintype "bidirectional"))
      (node (ref "J9") (pin "k24") (pinfunction "k24_k24") (pintype "bidirectional"))
      (node (ref "J9") (pin "k27") (pinfunction "k27_k27") (pintype "bidirectional"))
      (node (ref "J9") (pin "k3") (pinfunction "k3_k3") (pintype "bidirectional"))
      (node (ref "J9") (pin "k30") (pinfunction "k30_k30") (pintype "bidirectional"))
      (node (ref "J9") (pin "k33") (pinfunction "k33_k33") (pintype "bidirectional"))
      (node (ref "J9") (pin "k36") (pinfunction "k36_k36") (pintype "bidirectional"))
      (node (ref "J9") (pin "k39") (pinfunction "k39_k39") (pintype "bidirectional"))
      (node (ref "J9") (pin "k6") (pinfunction "k6_k6") (pintype "bidirectional"))
      (node (ref "J9") (pin "k9") (pinfunction "k9_k9") (pintype "bidirectional"))
    )
    (net (code "184") (name "P3V3") (class "Default")
      (node (ref "J9") (pin "c39") (pinfunction "c39_c39") (pintype "bidirectional"))
      (node (ref "J9") (pin "d36") (pinfunction "d36_d36") (pintype "bidirectional"))
      (node (ref "J9") (pin "d38") (pinfunction "d38_d38") (pintype "bidirectional"))
      (node (ref "J9") (pin "d40") (pinfunction "d40_d40") (pintype "bidirectional"))
      (node (ref "R74") (pin "1") (pinfunction "1_1") (pintype "passive"))
    )
    (net (code "185") (name "P12V0") (class "Default")
      (node (ref "J9") (pin "c35") (pinfunction "c35_c35") (pintype "bidirectional"))
      (node (ref "J9") (pin "c37") (pinfunction "c37_c37") (pintype "bidirectional"))
    )
    (net (code "186") (name "VADJ") (class "Default")
      (node (ref "J9") (pin "e39") (pinfunction "e39_e39") (pintype "bidirectional"))
      (node (ref "J9") (pin "f40") (pinfunction "f40_f40") (pintype "bidirectional"))
      (node (ref "J9") (pin "g39") (pinfunction "g39_g39") (pintype "bidirectional"))
      (node (ref "J9") (pin "h40") (pinfunction "h40_h40") (pintype "bidirectional"))
    )
    (net (code "187") (name "unconnected-(J9-Pada2)") (class "Default")
      (node (ref "J9") (pin "a2") (pinfunction "a2_a2") (pintype "bidirectional+no_connect"))
    )
    (net (code "188") (name "unconnected-(J9-Pada3)") (class "Default")
      (node (ref "J9") (pin "a3") (pinfunction "a3_a3") (pintype "bidirectional+no_connect"))
    )
    (net (code "189") (name "unconnected-(J9-Pada6)") (class "Default")
      (node (ref "J9") (pin "a6") (pinfunction "a6_a6") (pintype "bidirectional+no_connect"))
    )
    (net (code "190") (name "unconnected-(J9-Pada7)") (class "Default")
      (node (ref "J9") (pin "a7") (pinfunction "a7_a7") (pintype "bidirectional+no_connect"))
    )
    (net (code "191") (name "unconnected-(J9-Pada10)") (class "Default")
      (node (ref "J9") (pin "a10") (pinfunction "a10_a10") (pintype "bidirectional+no_connect"))
    )
    (net (code "192") (name "unconnected-(J9-Pada11)") (class "Default")
      (node (ref "J9") (pin "a11") (pinfunction "a11_a11") (pintype "bidirectional+no_connect"))
    )
    (net (code "193") (name "unconnected-(J9-Pada14)") (class "Default")
      (node (ref "J9") (pin "a14") (pinfunction "a14_a14") (pintype "bidirectional+no_connect"))
    )
    (net (code "194") (name "unconnected-(J9-Pada15)") (class "Default")
      (node (ref "J9") (pin "a15") (pinfunction "a15_a15") (pintype "bidirectional+no_connect"))
    )
    (net (code "195") (name "unconnected-(J9-Pada18)") (class "Default")
      (node (ref "J9") (pin "a18") (pinfunction "a18_a18") (pintype "bidirectional+no_connect"))
    )
    (net (code "196") (name "unconnected-(J9-Pada19)") (class "Default")
      (node (ref "J9") (pin "a19") (pinfunction "a19_a19") (pintype "bidirectional+no_connect"))
    )
    (net (code "197") (name "unconnected-(J9-Pada22)") (class "Default")
      (node (ref "J9") (pin "a22") (pinfunction "a22_a22") (pintype "bidirectional+no_connect"))
    )
    (net (code "198") (name "unconnected-(J9-Pada23)") (class "Default")
      (node (ref "J9") (pin "a23") (pinfunction "a23_a23") (pintype "bidirectional+no_connect"))
    )
    (net (code "199") (name "unconnected-(J9-Pada26)") (class "Default")
      (node (ref "J9") (pin "a26") (pinfunction "a26_a26") (pintype "bidirectional+no_connect"))
    )
    (net (code "200") (name "unconnected-(J9-Pada27)") (class "Default")
      (node (ref "J9") (pin "a27") (pinfunction "a27_a27") (pintype "bidirectional+no_connect"))
    )
    (net (code "201") (name "unconnected-(J9-Pada30)") (class "Default")
      (node (ref "J9") (pin "a30") (pinfunction "a30_a30") (pintype "bidirectional+no_connect"))
    )
    (net (code "202") (name "unconnected-(J9-Pada31)") (class "Default")
      (node (ref "J9") (pin "a31") (pinfunction "a31_a31") (pintype "bidirectional+no_connect"))
    )
    (net (code "203") (name "unconnected-(J9-Pada34)") (class "Default")
      (node (ref "J9") (pin "a34") (pinfunction "a34_a34") (pintype "bidirectional+no_connect"))
    )
    (net (code "204") (name "unconnected-(J9-Pada35)") (class "Default")
      (node (ref "J9") (pin "a35") (pinfunction "a35_a35") (pintype "bidirectional+no_connect"))
    )
    (net (code "205") (name "unconnected-(J9-Pada38)") (class "Default")
      (node (ref "J9") (pin "a38") (pinfunction "a38_a38") (pintype "bidirectional+no_connect"))
    )
    (net (code "206") (name "unconnected-(J9-Pada39)") (class "Default")
      (node (ref "J9") (pin "a39") (pinfunction "a39_a39") (pintype "bidirectional+no_connect"))
    )
    (net (code "207") (name "unconnected-(J9-Padb4)") (class "Default")
      (node (ref "J9") (pin "b4") (pinfunction "b4_b4") (pintype "bidirectional+no_connect"))
    )
    (net (code "208") (name "unconnected-(J9-Padb5)") (class "Default")
      (node (ref "J9") (pin "b5") (pinfunction "b5_b5") (pintype "bidirectional+no_connect"))
    )
    (net (code "209") (name "unconnected-(J9-Padb8)") (class "Default")
      (node (ref "J9") (pin "b8") (pinfunction "b8_b8") (pintype "bidirectional+no_connect"))
    )
    (net (code "210") (name "unconnected-(J9-Padb9)") (class "Default")
      (node (ref "J9") (pin "b9") (pinfunction "b9_b9") (pintype "bidirectional+no_connect"))
    )
    (net (code "211") (name "unconnected-(J9-Padb12)") (class "Default")
      (node (ref "J9") (pin "b12") (pinfunction "b12_b12") (pintype "bidirectional+no_connect"))
    )
    (net (code "212") (name "unconnected-(J9-Padb13)") (class "Default")
      (node (ref "J9") (pin "b13") (pinfunction "b13_b13") (pintype "bidirectional+no_connect"))
    )
    (net (code "213") (name "unconnected-(J9-Padb16)") (class "Default")
      (node (ref "J9") (pin "b16") (pinfunction "b16_b16") (pintype "bidirectional+no_connect"))
    )
    (net (code "214") (name "unconnected-(J9-Padb17)") (class "Default")
      (node (ref "J9") (pin "b17") (pinfunction "b17_b17") (pintype "bidirectional+no_connect"))
    )
    (net (code "215") (name "unconnected-(J9-Padb20)") (class "Default")
      (node (ref "J9") (pin "b20") (pinfunction "b20_b20") (pintype "bidirectional+no_connect"))
    )
    (net (code "216") (name "unconnected-(J9-Padb21)") (class "Default")
      (node (ref "J9") (pin "b21") (pinfunction "b21_b21") (pintype "bidirectional+no_connect"))
    )
    (net (code "217") (name "unconnected-(J9-Padb24)") (class "Default")
      (node (ref "J9") (pin "b24") (pinfunction "b24_b24") (pintype "bidirectional+no_connect"))
    )
    (net (code "218") (name "unconnected-(J9-Padb25)") (class "Default")
      (node (ref "J9") (pin "b25") (pinfunction "b25_b25") (pintype "bidirectional+no_connect"))
    )
    (net (code "219") (name "unconnected-(J9-Padb28)") (class "Default")
      (node (ref "J9") (pin "b28") (pinfunction "b28_b28") (pintype "bidirectional+no_connect"))
    )
    (net (code "220") (name "unconnected-(J9-Padb29)") (class "Default")
      (node (ref "J9") (pin "b29") (pinfunction "b29_b29") (pintype "bidirectional+no_connect"))
    )
    (net (code "221") (name "unconnected-(J9-Padb32)") (class "Default")
      (node (ref "J9") (pin "b32") (pinfunction "b32_b32") (pintype "bidirectional+no_connect"))
    )
    (net (code "222") (name "unconnected-(J9-Padb33)") (class "Default")
      (node (ref "J9") (pin "b33") (pinfunction "b33_b33") (pintype "bidirectional+no_connect"))
    )
    (net (code "223") (name "unconnected-(J9-Padb36)") (class "Default")
      (node (ref "J9") (pin "b36") (pinfunction "b36_b36") (pintype "bidirectional+no_connect"))
    )
    (net (code "224") (name "unconnected-(J9-Padb37)") (class "Default")
      (node (ref "J9") (pin "b37") (pinfunction "b37_b37") (pintype "bidirectional+no_connect"))
    )
    (net (code "225") (name "unconnected-(J9-Padb40)") (class "Default")
      (node (ref "J9") (pin "b40") (pinfunction "b40_b40") (pintype "bidirectional+no_connect"))
    )
    (net (code "226") (name "unconnected-(J9-Padc2)") (class "Default")
      (node (ref "J9") (pin "c2") (pinfunction "c2_c2") (pintype "bidirectional+no_connect"))
    )
    (net (code "227") (name "unconnected-(J9-Padc3)") (class "Default")
      (node (ref "J9") (pin "c3") (pinfunction "c3_c3") (pintype "bidirectional+no_connect"))
    )
    (net (code "228") (name "unconnected-(J9-Padc6)") (class "Default")
      (node (ref "J9") (pin "c6") (pinfunction "c6_c6") (pintype "bidirectional+no_connect"))
    )
    (net (code "229") (name "unconnected-(J9-Padc7)") (class "Default")
      (node (ref "J9") (pin "c7") (pinfunction "c7_c7") (pintype "bidirectional+no_connect"))
    )
    (net (code "230") (name "unconnected-(J9-Padd1)") (class "Default")
      (node (ref "J9") (pin "d1") (pinfunction "d1_d1") (pintype "bidirectional+no_connect"))
    )
    (net (code "231") (name "unconnected-(J9-Padd4)") (class "Default")
      (node (ref "J9") (pin "d4") (pinfunction "d4_d4") (pintype "bidirectional+no_connect"))
    )
    (net (code "232") (name "unconnected-(J9-Padd5)") (class "Default")
      (node (ref "J9") (pin "d5") (pinfunction "d5_d5") (pintype "bidirectional+no_connect"))
    )
    (net (code "233") (name "unconnected-(J9-Padd29)") (class "Default")
      (node (ref "J9") (pin "d29") (pinfunction "d29_d29") (pintype "bidirectional+no_connect"))
    )
    (net (code "234") (name "unconnected-(J9-Padd33)") (class "Default")
      (node (ref "J9") (pin "d33") (pinfunction "d33_d33") (pintype "bidirectional+no_connect"))
    )
    (net (code "235") (name "unconnected-(J9-Padd34)") (class "Default")
      (node (ref "J9") (pin "d34") (pinfunction "d34_d34") (pintype "bidirectional+no_connect"))
    )
    (net (code "236") (name "unconnected-(J9-Padk1)") (class "Default")
      (node (ref "J9") (pin "k1") (pinfunction "k1_k1") (pintype "bidirectional+no_connect"))
    )
  )
)
